# DIO.net
KiCad netlist of a schematic drawn in Altium Designer
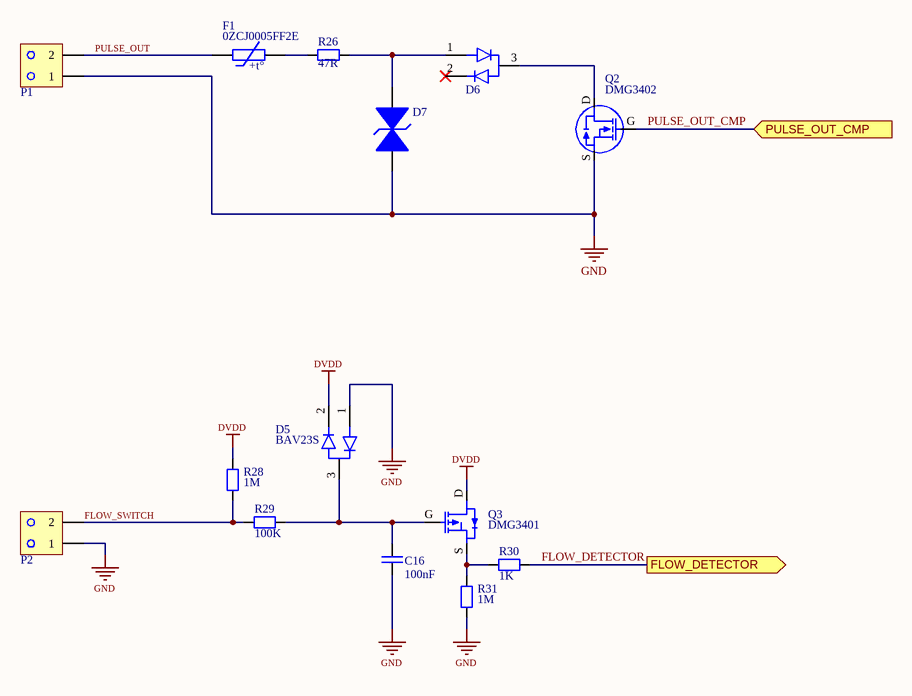
[diagram p0: DIO.SchDoc]

(export (version "E")
  (design (tool "Eeschema 10.0.6"))
  (components
    (comp (ref "C16")
      (value "100nF")
      (footprint "CAP_SM0805_YAGEOCC2_N")
      (description "CAP 100nF SM0805 X7R 25V YAGEO CC2")
      (fields
        (field (name "MANUFACTURER") "Yageo")
        (field (name "MANUFACTURER PART NUMBER") "CC0805KRX7R8BB104")
      )
      (libsource (lib "Yageo") (part "CC0805KRX7R8BB104"))
    )
    (comp (ref "D5")
      (value "BAV23S")
      (footprint "BAV23S")
      (description "DIODE ARRAY GP 250V 200MA SOT23")
      (fields (field (name "MANUFACTURER") "onsemi"))
      (libsource (lib "diode") (part "BAV23S"))
    )
    (comp (ref "D6")
      (value "BAV23S")
      (footprint "BAV23S")
      (description "DIODE ARRAY GP 250V 200MA SOT23")
      (fields (field (name "MANUFACTURER") "onsemi"))
      (libsource (lib "diode") (part "BAV23S"))
    )
    (comp (ref "D7")
      (value "SMBJ28CA-13-F")
      (footprint "SMBJ28CA-13-F")
      (fields (field (name "MANUFACTURER") "BORN") (field (name "MANUFACTURER PART NUMBER") "SMBJ24CA"))
      (libsource (lib "diode") (part "SMBJ28CA-13-F"))
    )
    (comp (ref "F1")
      (value "0ZCJ0005FF2E")
      (footprint "0ZCJ0005FF2E")
      (description "PTC RESET FUSE 60V 50MA 1206")
      (fields (field (name "MANUFACTURER") "Bel Fuse Inc."))
      (libsource (lib "fuse") (part "0ZCJ0005FF2E"))
    )
    (comp (ref "P1")
      (value "WJ15EDGVC-3.81-2P")
      (footprint "HEADER PLUG 2")
      (description "TERM BLOK FEMALE 1X2 3.81MM")
      (fields (field (name "MANUFACTURER") "Ningbo Kangnex Elec"))
      (libsource (lib "plug") (part "WJ15EDGVC-3.81-2P"))
    )
    (comp (ref "P2")
      (value "WJ15EDGVC-3.81-2P")
      (footprint "HEADER PLUG 2")
      (description "TERM BLOK FEMALE 1X2 3.81MM")
      (fields (field (name "MANUFACTURER") "Ningbo Kangnex Elec"))
      (libsource (lib "plug") (part "WJ15EDGVC-3.81-2P"))
    )
    (comp (ref "Q2")
      (value "DMG3402")
      (footprint "DMG3402L-7")
      (description "N-CHANNEL ENHANCEMENT MODE FIELD EFFECT TRANSISTOR\r\n85mΩ @ VGS = 2.5V -> ID 2A\r\nV(BR)DDS 30V")
      (fields
        (field (name "MANUFACTURER") "Diodes Incorporated")
        (field (name "MANUFACTURER PART NUMBER") "DMG3402L-7")
      )
      (libsource (lib "mosfet") (part "DMG3402L-7"))
    )
    (comp (ref "Q3")
      (value "DMG3401")
      (footprint "DMG3401LSN-7")
      (description "P-CHANNEL ENHANCEMENT MODE MOSFET\r\nRDS(ON) = 85mΩ @ VGS = -2.5V -> ID -2.7A\r\nV(BR)DDS 30V")
      (fields
        (field (name "MANUFACTURER") "Diodes Incorporated")
        (field (name "MANUFACTURER PART NUMBER") "DMG3401LSN-7")
      )
      (libsource (lib "mosfet") (part "DMG3401LSN-7"))
    )
    (comp (ref "R26")
      (value "47R")
      (footprint "RES_SM0805_YAGEORC_N")
      (description "RES 47R SM0805 YAGEO RC_L")
      (fields
        (field (name "MANUFACTURER") "Yageo")
        (field (name "MANUFACTURER PART NUMBER") "RC0805FR-0747RL")
      )
      (libsource (lib "Yageo") (part "RC0805FR-0747RL"))
    )
    (comp (ref "R28")
      (value "1M")
      (footprint "RES_SM0805_YAGEORC_N")
      (description "RES 1M SM0805 YAGEO RC_L")
      (fields
        (field (name "MANUFACTURER") "Yageo")
        (field (name "MANUFACTURER PART NUMBER") "RC0805FR-071ML")
      )
      (libsource (lib "Yageo") (part "RC0805FR-071ML"))
    )
    (comp (ref "R29")
      (value "100K")
      (footprint "RES_SM0805_YAGEORC_N")
      (description "RES 100K SM0805 YAGEO RC_L")
      (fields
        (field (name "MANUFACTURER") "Yageo")
        (field (name "MANUFACTURER PART NUMBER") "RC0805FR-07100KL")
      )
      (libsource (lib "Yageo") (part "RC0805FR-07100KL"))
    )
    (comp (ref "R30")
      (value "1K")
      (footprint "RES_SM0805_YAGEORC_N")
      (description "RES 1K SM0805 YAGEO RC_L")
      (fields
        (field (name "MANUFACTURER") "Yageo")
        (field (name "MANUFACTURER PART NUMBER") "RC0805FR-071KL")
      )
      (libsource (lib "Yageo") (part "RC0805FR-071KL"))
    )
    (comp (ref "R31")
      (value "1M")
      (footprint "RES_SM0805_YAGEORC_N")
      (description "RES 1M SM0805 YAGEO RC_L")
      (fields
        (field (name "MANUFACTURER") "Yageo")
        (field (name "MANUFACTURER PART NUMBER") "RC0805FR-071ML")
      )
      (libsource (lib "Yageo") (part "RC0805FR-071ML"))
    )
  )
  (nets
    (net (code "1") (name "/FLOW_DETECTOR") (class "Default")
      (node (ref "R30") (pin "2") (pintype "passive"))
    )
    (net (code "2") (name "/FLOW_SWITCH") (class "Default")
      (node (ref "P2") (pin "2") (pinfunction "2_2") (pintype "passive"))
      (node (ref "R28") (pin "1") (pintype "passive"))
      (node (ref "R29") (pin "1") (pintype "passive"))
    )
    (net (code "3") (name "/PULSE_OUT") (class "Default")
      (node (ref "F1") (pin "1") (pinfunction "1_1") (pintype "passive"))
      (node (ref "P1") (pin "2") (pinfunction "2_2") (pintype "passive"))
    )
    (net (code "4") (name "/PULSE_OUT_CMP") (class "Default")
      (node (ref "Q2") (pin "G") (pinfunction "G_G") (pintype "passive"))
    )
    (net (code "5") (name "DVDD") (class "Default")
      (node (ref "D5") (pin "2") (pinfunction "2_2") (pintype "passive"))
      (node (ref "Q3") (pin "D") (pinfunction "D_D") (pintype "passive"))
      (node (ref "R28") (pin "2") (pintype "passive"))
    )
    (net (code "6") (name "GND") (class "Default")
      (node (ref "C16") (pin "2") (pintype "passive"))
      (node (ref "D5") (pin "1") (pinfunction "1_1") (pintype "passive"))
      (node (ref "D7") (pin "A") (pinfunction "A_A") (pintype "passive"))
      (node (ref "P1") (pin "1") (pinfunction "1_1") (pintype "passive"))
      (node (ref "P2") (pin "1") (pinfunction "1_1") (pintype "passive"))
      (node (ref "Q2") (pin "S") (pinfunction "S_S") (pintype "passive"))
      (node (ref "R31") (pin "1") (pintype "passive"))
    )
    (net (code "7") (name "Net-(C16-Pad1)") (class "Default")
      (node (ref "C16") (pin "1") (pintype "passive"))
      (node (ref "D5") (pin "3") (pinfunction "3_3") (pintype "passive"))
      (node (ref "Q3") (pin "G") (pinfunction "G_G") (pintype "passive"))
      (node (ref "R29") (pin "2") (pintype "passive"))
    )
    (net (code "8") (name "Net-(D6-Pad1)") (class "Default")
      (node (ref "D6") (pin "1") (pinfunction "1_1") (pintype "passive"))
      (node (ref "D7") (pin "K") (pinfunction "K_K") (pintype "passive"))
      (node (ref "R26") (pin "1") (pintype "passive"))
    )
    (net (code "9") (name "Net-(D6-Pad3)") (class "Default")
      (node (ref "D6") (pin "3") (pinfunction "3_3") (pintype "passive"))
      (node (ref "Q2") (pin "D") (pinfunction "D_D") (pintype "passive"))
    )
    (net (code "10") (name "Net-(F1-Pad2)") (class "Default")
      (node (ref "F1") (pin "2") (pinfunction "2_2") (pintype "passive"))
      (node (ref "R26") (pin "2") (pintype "passive"))
    )
    (net (code "11") (name "Net-(Q3-PadS)") (class "Default")
      (node (ref "Q3") (pin "S") (pinfunction "S_S") (pintype "passive"))
      (node (ref "R30") (pin "1") (pintype "passive"))
      (node (ref "R31") (pin "2") (pintype "passive"))
    )
    (net (code "12") (name "unconnected-(D6-Pad2)") (class "Default")
      (node (ref "D6") (pin "2") (pinfunction "2_2") (pintype "passive+no_connect"))
    )
  )
)
